# mailbox-sensor.net
KiCad netlist of a schematic drawn in EAGLE
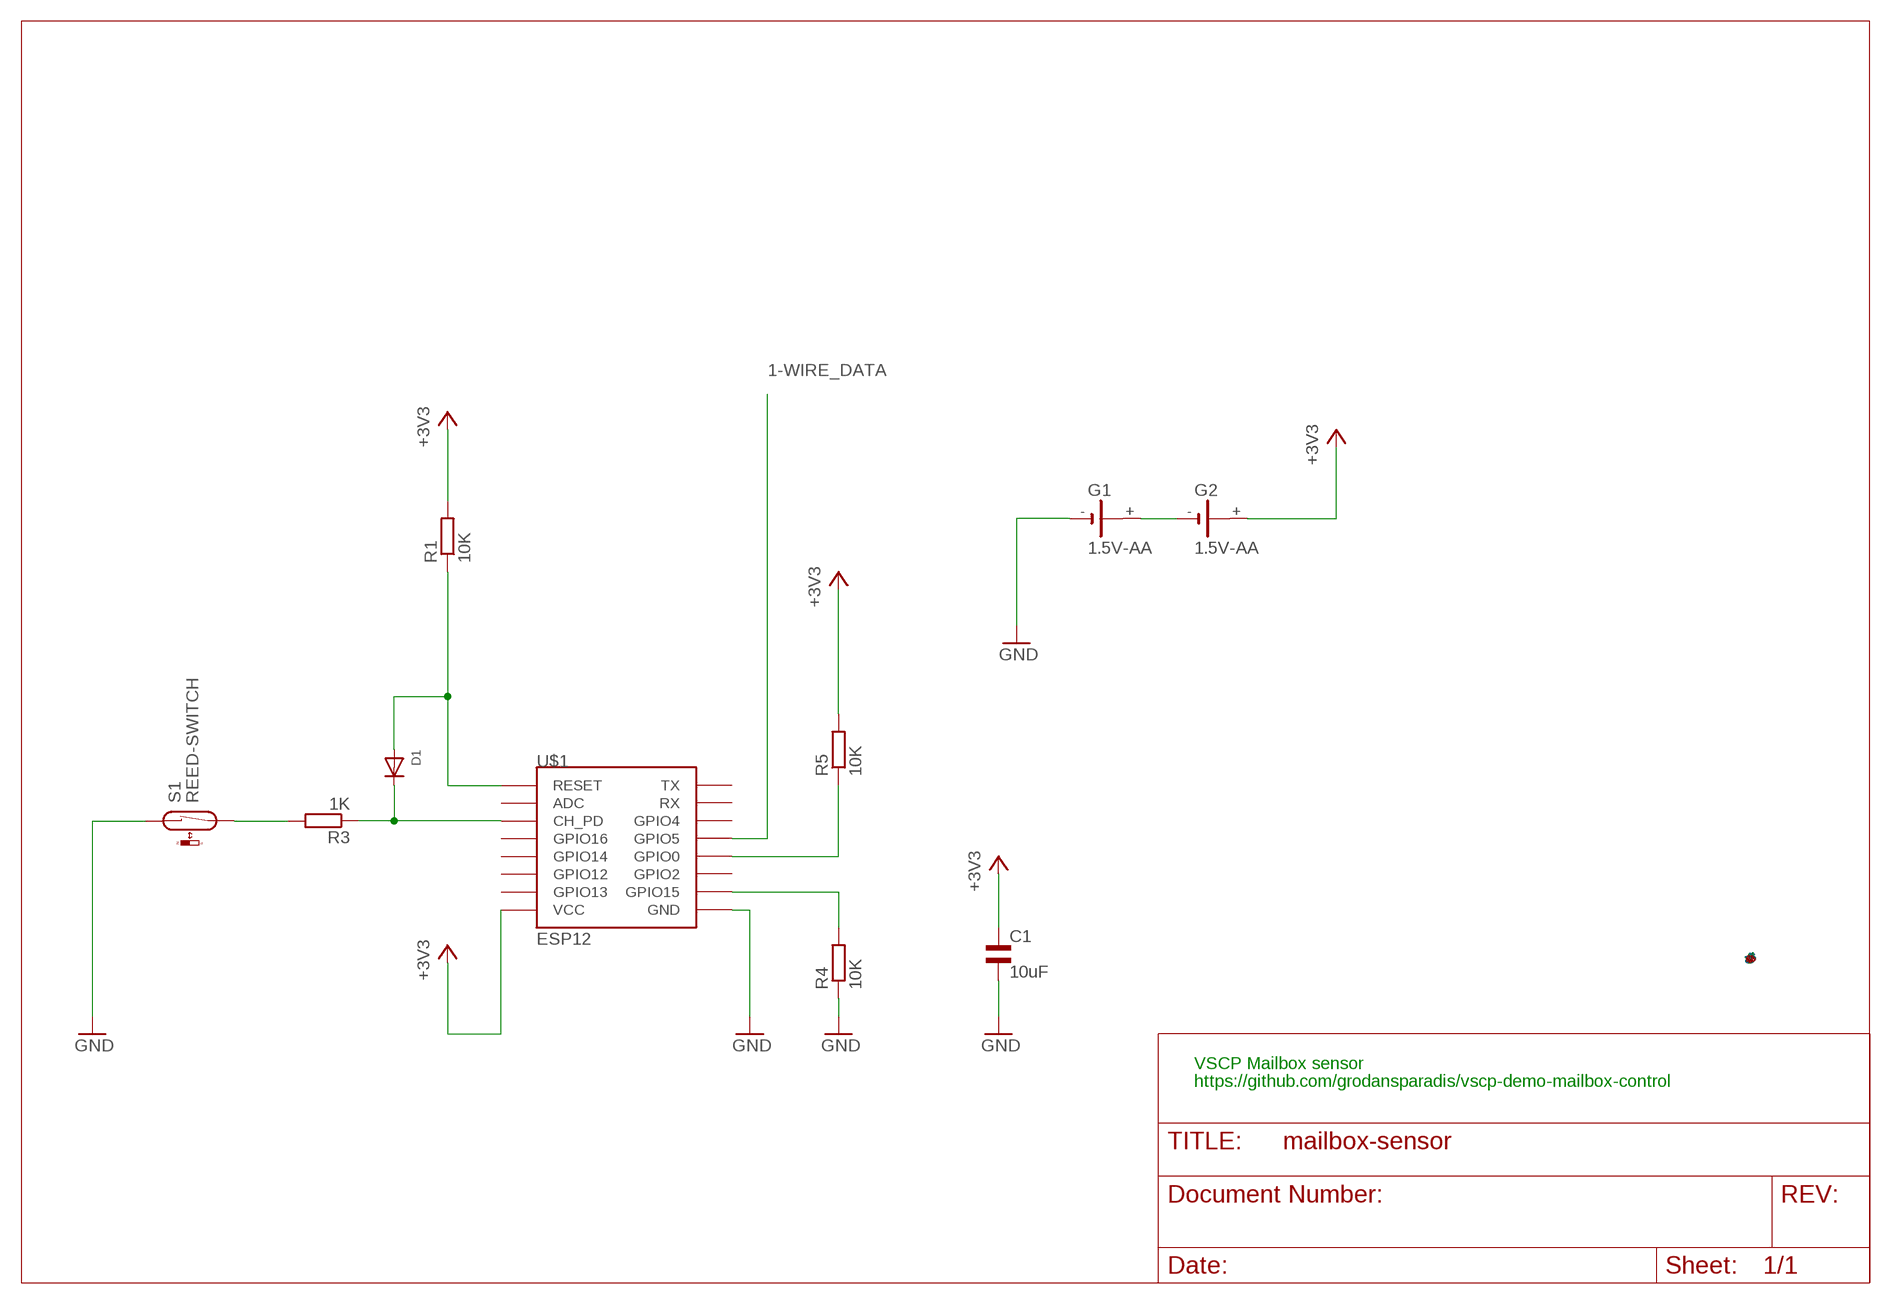
[diagram p0: schematic, sheet 1]

(export (version "E")
  (design (tool "Eeschema 10.0.6"))
  (components
    (comp (ref "C1")
      (value "10uF")
      (footprint "eagle-import:EU35-12")
      (libsource (lib "eagle-import") (part "EL-BI35-12AXIAL"))
    )
    (comp (ref "D1")
      (value "DIODEDO-1N4148")
      (footprint "eagle-import:DO-1N4148")
      (libsource (lib "eagle-import") (part "DIODEDO-1N4148"))
    )
    (comp (ref "G1")
      (value "1.5V-AA")
      (footprint "eagle-import:CRAA")
      (libsource (lib "eagle-import") (part "CR-AA"))
    )
    (comp (ref "G2")
      (value "1.5V-AA")
      (footprint "eagle-import:CRAA")
      (libsource (lib "eagle-import") (part "CR-AA"))
    )
    (comp (ref "R1")
      (value "10K")
      (footprint "eagle-import:M0805")
      (libsource (lib "eagle-import") (part "R-EU_M0805"))
    )
    (comp (ref "R3")
      (value "1K")
      (footprint "eagle-import:M0805")
      (libsource (lib "eagle-import") (part "R-EU_M0805"))
    )
    (comp (ref "R4")
      (value "10K")
      (footprint "eagle-import:M0805")
      (libsource (lib "eagle-import") (part "R-EU_M0805"))
    )
    (comp (ref "R5")
      (value "10K")
      (footprint "eagle-import:M0805")
      (libsource (lib "eagle-import") (part "R-EU_M0805"))
    )
    (comp (ref "S1")
      (value "REED-SWITCH")
      (footprint "eagle-import:CT10-G4")
      (libsource (lib "eagle-import") (part "REED-SWITCH-CT10-G4"))
    )
    (comp (ref "U$1")
      (value "ESP12")
      (footprint "eagle-import:ESP12")
      (libsource (lib "eagle-import") (part "ESP12"))
    )
    (comp (ref "U$2")
      (value "VSCP_LOGO")
      (footprint "eagle-import:VSCP_LOGO")
      (libsource (lib "eagle-import") (part "VSCP_LOGO"))
    )
  )
  (nets
    (net (code "1") (name "+3V3") (class "Default")
      (node (ref "C1") (pin "1") (pinfunction "1_1") (pintype "passive"))
      (node (ref "G2") (pin "+") (pinfunction "+_+") (pintype "passive"))
      (node (ref "R1") (pin "2") (pinfunction "2_2") (pintype "passive"))
      (node (ref "R5") (pin "2") (pinfunction "2_2") (pintype "passive"))
      (node (ref "U$1") (pin "VCC") (pinfunction "VCC_VCC") (pintype "bidirectional"))
    )
    (net (code "2") (name "/1-WIRE_DATA") (class "Default")
      (node (ref "U$1") (pin "GPIO5") (pinfunction "GPIO5_GPIO5") (pintype "bidirectional"))
    )
    (net (code "3") (name "GND") (class "Default")
      (node (ref "C1") (pin "2") (pinfunction "2_2") (pintype "passive"))
      (node (ref "G1") (pin "-") (pinfunction "-_-") (pintype "passive"))
      (node (ref "R4") (pin "1") (pinfunction "1_1") (pintype "passive"))
      (node (ref "S1") (pin "1") (pinfunction "1_1") (pintype "passive"))
      (node (ref "U$1") (pin "GND") (pinfunction "GND_GND") (pintype "bidirectional"))
    )
    (net (code "4") (name "Net-(D1-PadA)") (class "Default")
      (node (ref "D1") (pin "A") (pinfunction "A_A") (pintype "passive"))
      (node (ref "R1") (pin "1") (pinfunction "1_1") (pintype "passive"))
      (node (ref "U$1") (pin "RESET") (pinfunction "RESET_RESET") (pintype "bidirectional"))
    )
    (net (code "5") (name "Net-(D1-PadC)") (class "Default")
      (node (ref "D1") (pin "C") (pinfunction "C_C") (pintype "passive"))
      (node (ref "R3") (pin "1") (pinfunction "1_1") (pintype "passive"))
      (node (ref "U$1") (pin "CH_PD") (pinfunction "CH_PD_CH_PD") (pintype "bidirectional"))
    )
    (net (code "6") (name "Net-(G1-Pad+)") (class "Default")
      (node (ref "G1") (pin "+") (pinfunction "+_+") (pintype "passive"))
      (node (ref "G2") (pin "-") (pinfunction "-_-") (pintype "passive"))
    )
    (net (code "7") (name "Net-(R3-Pad2)") (class "Default")
      (node (ref "R3") (pin "2") (pinfunction "2_2") (pintype "passive"))
      (node (ref "S1") (pin "2") (pinfunction "2_2") (pintype "passive"))
    )
    (net (code "8") (name "Net-(R4-Pad2)") (class "Default")
      (node (ref "R4") (pin "2") (pinfunction "2_2") (pintype "passive"))
      (node (ref "U$1") (pin "GPIO15") (pinfunction "GPIO15_GPIO15") (pintype "bidirectional"))
    )
    (net (code "9") (name "Net-(R5-Pad1)") (class "Default")
      (node (ref "R5") (pin "1") (pinfunction "1_1") (pintype "passive"))
      (node (ref "U$1") (pin "GPIO0") (pinfunction "GPIO0_GPIO0") (pintype "bidirectional"))
    )
    (net (code "10") (name "unconnected-(G1-+-Pad+@1)") (class "Default")
      (node (ref "G1") (pin "+@1") (pinfunction "+_+@1") (pintype "passive"))
    )
    (net (code "11") (name "unconnected-(G2-+-Pad+@1)") (class "Default")
      (node (ref "G2") (pin "+@1") (pinfunction "+_+@1") (pintype "passive"))
    )
    (net (code "12") (name "unconnected-(U$1-PadADC)") (class "Default")
      (node (ref "U$1") (pin "ADC") (pinfunction "ADC_ADC") (pintype "bidirectional"))
    )
    (net (code "13") (name "unconnected-(U$1-PadGPIO2)") (class "Default")
      (node (ref "U$1") (pin "GPIO2") (pinfunction "GPIO2_GPIO2") (pintype "bidirectional"))
    )
    (net (code "14") (name "unconnected-(U$1-PadGPIO4)") (class "Default")
      (node (ref "U$1") (pin "GPIO4") (pinfunction "GPIO4_GPIO4") (pintype "bidirectional"))
    )
    (net (code "15") (name "unconnected-(U$1-PadGPIO12)") (class "Default")
      (node (ref "U$1") (pin "GPIO12") (pinfunction "GPIO12_GPIO12") (pintype "bidirectional"))
    )
    (net (code "16") (name "unconnected-(U$1-PadGPIO13)") (class "Default")
      (node (ref "U$1") (pin "GPIO13") (pinfunction "GPIO13_GPIO13") (pintype "bidirectional"))
    )
    (net (code "17") (name "unconnected-(U$1-PadGPIO14)") (class "Default")
      (node (ref "U$1") (pin "GPIO14") (pinfunction "GPIO14_GPIO14") (pintype "bidirectional"))
    )
    (net (code "18") (name "unconnected-(U$1-PadGPIO16)") (class "Default")
      (node (ref "U$1") (pin "GPIO16") (pinfunction "GPIO16_GPIO16") (pintype "bidirectional"))
    )
    (net (code "19") (name "unconnected-(U$1-PadRX)") (class "Default")
      (node (ref "U$1") (pin "RX") (pinfunction "RX_RX") (pintype "bidirectional"))
    )
    (net (code "20") (name "unconnected-(U$1-PadTX)") (class "Default")
      (node (ref "U$1") (pin "TX") (pinfunction "TX_TX") (pintype "bidirectional"))
    )
  )
)
